# magnet_wiring_breakout.net
KiCad netlist of a schematic drawn in EAGLE
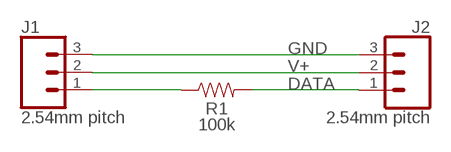
[diagram p0: schematic, sheet 1]

(export (version "E")
  (design (tool "Eeschema 10.0.6"))
  (components
    (comp (ref "J1")
      (value "2.54mm pitch")
      (footprint "eagle-import:1X03")
      (libsource (lib "eagle-import") (part "CONN_03"))
    )
    (comp (ref "J2")
      (value "2.54mm pitch")
      (footprint "eagle-import:1X03")
      (libsource (lib "eagle-import") (part "CONN_03"))
    )
    (comp (ref "R1")
      (value "100k")
      (footprint "eagle-import:0805")
      (libsource (lib "eagle-import") (part "RESISTOR0805"))
    )
  )
  (nets
    (net (code "1") (name "/DATA") (class "Default")
      (node (ref "J2") (pin "1") (pinfunction "1_1") (pintype "passive"))
      (node (ref "R1") (pin "2") (pinfunction "2_2") (pintype "passive"))
    )
    (net (code "2") (name "/GND") (class "Default")
      (node (ref "J1") (pin "3") (pinfunction "3_3") (pintype "passive"))
      (node (ref "J2") (pin "3") (pinfunction "3_3") (pintype "passive"))
    )
    (net (code "3") (name "/V+") (class "Default")
      (node (ref "J1") (pin "2") (pinfunction "2_2") (pintype "passive"))
      (node (ref "J2") (pin "2") (pinfunction "2_2") (pintype "passive"))
    )
    (net (code "4") (name "Net-(J1-Pad1)") (class "Default")
      (node (ref "J1") (pin "1") (pinfunction "1_1") (pintype "passive"))
      (node (ref "R1") (pin "1") (pinfunction "1_1") (pintype "passive"))
    )
  )
)
